# TCA0372_3x.net
KiCad netlist of a schematic drawn in EAGLE
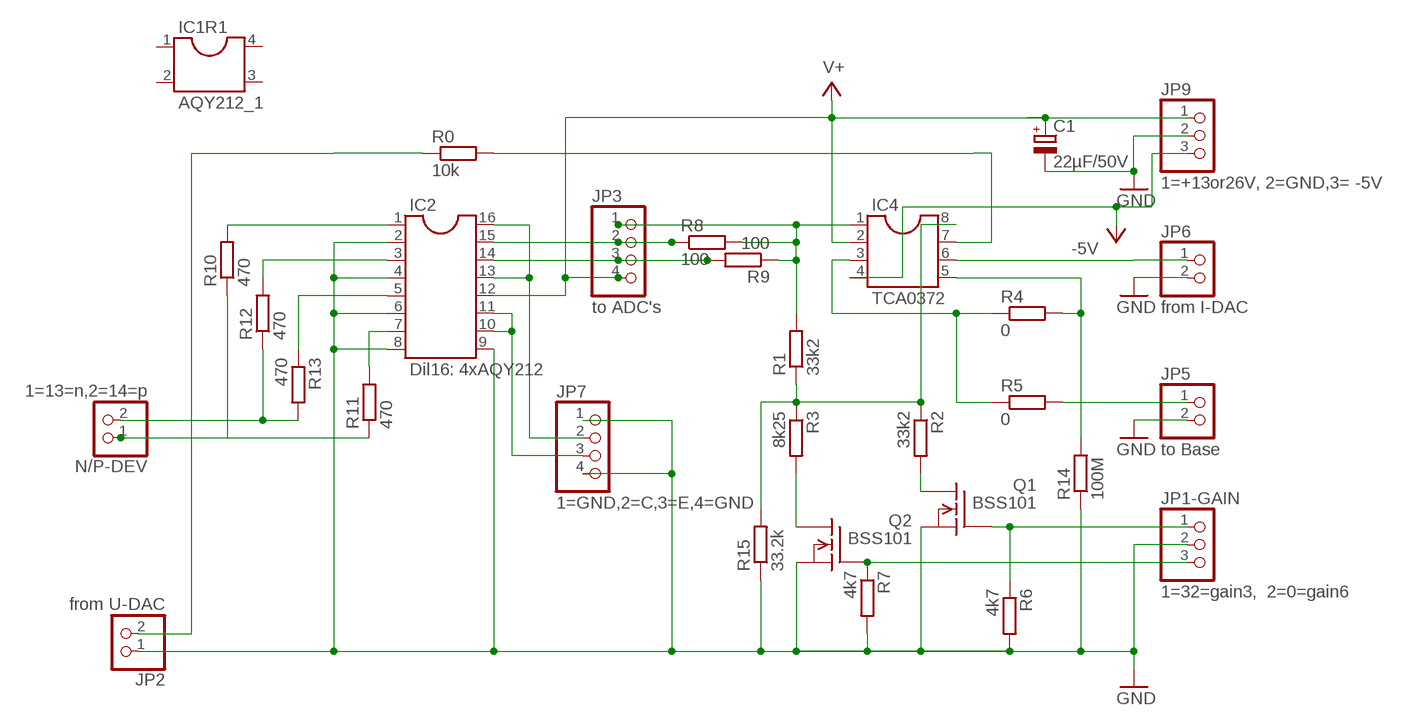
[diagram p0: schematic, sheet 1]

(export (version "E")
  (design (tool "Eeschema 10.0.6"))
  (components
    (comp (ref "C1")
      (value "22µF/50V")
      (footprint "eagle-import:E5-10,5")
      (libsource (lib "eagle-import") (part "CPOL-EUE5-10.5"))
    )
    (comp (ref "IC1R1")
      (value "AQY212_1")
      (footprint "eagle-import:SOCKET-04")
      (libsource (lib "eagle-import") (part "DIL4S"))
    )
    (comp (ref "IC2")
      (value "Dil16: 4xAQY212")
      (footprint "eagle-import:SOCKET-16")
      (libsource (lib "eagle-import") (part "DIL16S"))
    )
    (comp (ref "IC4")
      (value "TCA0372")
      (footprint "eagle-import:SOCKET-08")
      (libsource (lib "eagle-import") (part "DIL8S"))
    )
    (comp (ref "JP1-GAIN")
      (value "1=32=gain3, 2=0=gain6")
      (footprint "eagle-import:1X03")
      (libsource (lib "eagle-import") (part "PINHD-1X3"))
    )
    (comp (ref "JP2")
      (value "from U-DAC")
      (footprint "eagle-import:1X02")
      (libsource (lib "eagle-import") (part "PINHD-1X2"))
    )
    (comp (ref "JP3")
      (value "to ADC's")
      (footprint "eagle-import:1X04")
      (libsource (lib "eagle-import") (part "PINHD-1X4"))
    )
    (comp (ref "JP5")
      (value "to Base")
      (footprint "eagle-import:1X02")
      (libsource (lib "eagle-import") (part "PINHD-1X2"))
    )
    (comp (ref "JP6")
      (value "from I-DAC")
      (footprint "eagle-import:1X02")
      (libsource (lib "eagle-import") (part "PINHD-1X2"))
    )
    (comp (ref "JP7")
      (value "1=GND,2=C,3=E,4=GND")
      (footprint "eagle-import:1X04")
      (libsource (lib "eagle-import") (part "PINHD-1X4"))
    )
    (comp (ref "JP9")
      (value "1=+13or26V, 2=GND,3= -5V")
      (footprint "eagle-import:1X03")
      (libsource (lib "eagle-import") (part "PINHD-1X3"))
    )
    (comp (ref "N/P-DEV")
      (value "1=13=n,2=14=p")
      (footprint "eagle-import:1X02")
      (libsource (lib "eagle-import") (part "PINHD-1X2"))
    )
    (comp (ref "Q1")
      (value "BSS101")
      (footprint "eagle-import:TO92")
      (libsource (lib "eagle-import") (part "BSS101"))
    )
    (comp (ref "Q2")
      (value "BSS101")
      (footprint "eagle-import:TO92")
      (libsource (lib "eagle-import") (part "BSS101"))
    )
    (comp (ref "R0")
      (value "10k")
      (footprint "eagle-import:0207_7")
      (libsource (lib "eagle-import") (part "R-EU_0207/7"))
    )
    (comp (ref "R1")
      (value "33k2")
      (footprint "eagle-import:0207_7")
      (libsource (lib "eagle-import") (part "R-EU_0207/7"))
    )
    (comp (ref "R2")
      (value "33k2")
      (footprint "eagle-import:0207_7")
      (libsource (lib "eagle-import") (part "R-EU_0207/7"))
    )
    (comp (ref "R3")
      (value "8k25")
      (footprint "eagle-import:0207_7")
      (libsource (lib "eagle-import") (part "R-EU_0207/7"))
    )
    (comp (ref "R4")
      (value "0")
      (footprint "eagle-import:0207_7")
      (libsource (lib "eagle-import") (part "R-EU_0207/7"))
    )
    (comp (ref "R5")
      (value "0")
      (footprint "eagle-import:0207_7")
      (libsource (lib "eagle-import") (part "R-EU_0207/7"))
    )
    (comp (ref "R6")
      (value "4k7")
      (footprint "eagle-import:0207_7")
      (libsource (lib "eagle-import") (part "R-EU_0207/7"))
    )
    (comp (ref "R7")
      (value "4k7")
      (footprint "eagle-import:0207_7")
      (libsource (lib "eagle-import") (part "R-EU_0207/7"))
    )
    (comp (ref "R8")
      (value "100")
      (footprint "eagle-import:0207_7")
      (libsource (lib "eagle-import") (part "R-EU_0207/7"))
    )
    (comp (ref "R9")
      (value "100")
      (footprint "eagle-import:0207_7")
      (libsource (lib "eagle-import") (part "R-EU_0207/7"))
    )
    (comp (ref "R10")
      (value "470")
      (footprint "eagle-import:0207_7")
      (libsource (lib "eagle-import") (part "R-EU_0207/7"))
    )
    (comp (ref "R11")
      (value "470")
      (footprint "eagle-import:0207_7")
      (libsource (lib "eagle-import") (part "R-EU_0207/7"))
    )
    (comp (ref "R12")
      (value "470")
      (footprint "eagle-import:0207_7")
      (libsource (lib "eagle-import") (part "R-EU_0207/7"))
    )
    (comp (ref "R13")
      (value "470")
      (footprint "eagle-import:0207_7")
      (libsource (lib "eagle-import") (part "R-EU_0207/7"))
    )
    (comp (ref "R14")
      (value "100M")
      (footprint "eagle-import:0207_7")
      (libsource (lib "eagle-import") (part "R-EU_0207/7"))
    )
    (comp (ref "R15")
      (value "33.2k")
      (footprint "eagle-import:0207_7")
      (libsource (lib "eagle-import") (part "R-EU_0207/7"))
    )
  )
  (nets
    (net (code "1") (name "-5V") (class "Default")
      (node (ref "IC4") (pin "4") (pinfunction "4_4") (pintype "passive"))
      (node (ref "JP9") (pin "3") (pinfunction "3_3") (pintype "passive"))
    )
    (net (code "2") (name "GND") (class "Default")
      (node (ref "C1") (pin "-") (pinfunction "-_-") (pintype "passive"))
      (node (ref "IC2") (pin "2") (pinfunction "2_2") (pintype "passive"))
      (node (ref "IC2") (pin "4") (pinfunction "4_4") (pintype "passive"))
      (node (ref "IC2") (pin "6") (pinfunction "6_6") (pintype "passive"))
      (node (ref "IC2") (pin "8") (pinfunction "8_8") (pintype "passive"))
      (node (ref "IC2") (pin "9") (pinfunction "9_9") (pintype "passive"))
      (node (ref "JP1-GAIN") (pin "2") (pinfunction "2_2") (pintype "passive"))
      (node (ref "JP2") (pin "1") (pinfunction "1_1") (pintype "passive"))
      (node (ref "JP5") (pin "2") (pinfunction "2_2") (pintype "passive"))
      (node (ref "JP6") (pin "2") (pinfunction "2_2") (pintype "passive"))
      (node (ref "JP7") (pin "1") (pinfunction "1_1") (pintype "passive"))
      (node (ref "JP7") (pin "4") (pinfunction "4_4") (pintype "passive"))
      (node (ref "JP9") (pin "2") (pinfunction "2_2") (pintype "passive"))
      (node (ref "Q1") (pin "1") (pinfunction "S_1") (pintype "passive"))
      (node (ref "Q2") (pin "1") (pinfunction "S_1") (pintype "passive"))
      (node (ref "R14") (pin "1") (pinfunction "1_1") (pintype "passive"))
      (node (ref "R15") (pin "1") (pinfunction "1_1") (pintype "passive"))
      (node (ref "R6") (pin "2") (pinfunction "2_2") (pintype "passive"))
      (node (ref "R7") (pin "2") (pinfunction "2_2") (pintype "passive"))
    )
    (net (code "3") (name "Net-(IC2-Pad1)") (class "Default")
      (node (ref "IC2") (pin "1") (pinfunction "1_1") (pintype "passive"))
      (node (ref "R10") (pin "2") (pinfunction "2_2") (pintype "passive"))
    )
    (net (code "4") (name "Net-(IC2-Pad3)") (class "Default")
      (node (ref "IC2") (pin "3") (pinfunction "3_3") (pintype "passive"))
      (node (ref "R12") (pin "2") (pinfunction "2_2") (pintype "passive"))
    )
    (net (code "5") (name "Net-(IC2-Pad5)") (class "Default")
      (node (ref "IC2") (pin "5") (pinfunction "5_5") (pintype "passive"))
      (node (ref "R13") (pin "1") (pinfunction "1_1") (pintype "passive"))
    )
    (net (code "6") (name "Net-(IC2-Pad7)") (class "Default")
      (node (ref "IC2") (pin "7") (pinfunction "7_7") (pintype "passive"))
      (node (ref "R11") (pin "2") (pinfunction "2_2") (pintype "passive"))
    )
    (net (code "7") (name "Net-(IC2-Pad10)") (class "Default")
      (node (ref "IC2") (pin "10") (pinfunction "10_10") (pintype "passive"))
      (node (ref "IC2") (pin "11") (pinfunction "11_11") (pintype "passive"))
      (node (ref "JP7") (pin "3") (pinfunction "3_3") (pintype "passive"))
    )
    (net (code "8") (name "Net-(IC2-Pad13)") (class "Default")
      (node (ref "IC2") (pin "13") (pinfunction "13_13") (pintype "passive"))
      (node (ref "IC2") (pin "16") (pinfunction "16_16") (pintype "passive"))
      (node (ref "JP7") (pin "2") (pinfunction "2_2") (pintype "passive"))
    )
    (net (code "9") (name "Net-(IC2-Pad14)") (class "Default")
      (node (ref "IC2") (pin "14") (pinfunction "14_14") (pintype "passive"))
      (node (ref "JP3") (pin "3") (pinfunction "3_3") (pintype "passive"))
      (node (ref "R9") (pin "2") (pinfunction "2_2") (pintype "passive"))
    )
    (net (code "10") (name "Net-(IC2-Pad15)") (class "Default")
      (node (ref "IC2") (pin "15") (pinfunction "15_15") (pintype "passive"))
      (node (ref "JP3") (pin "2") (pinfunction "2_2") (pintype "passive"))
      (node (ref "R8") (pin "1") (pinfunction "1_1") (pintype "passive"))
    )
    (net (code "11") (name "Net-(IC4-Pad1)") (class "Default")
      (node (ref "IC4") (pin "1") (pinfunction "1_1") (pintype "passive"))
      (node (ref "JP3") (pin "1") (pinfunction "1_1") (pintype "passive"))
      (node (ref "R1") (pin "2") (pinfunction "2_2") (pintype "passive"))
      (node (ref "R8") (pin "2") (pinfunction "2_2") (pintype "passive"))
      (node (ref "R9") (pin "1") (pinfunction "1_1") (pintype "passive"))
    )
    (net (code "12") (name "Net-(IC4-Pad3)") (class "Default")
      (node (ref "IC4") (pin "3") (pinfunction "3_3") (pintype "passive"))
      (node (ref "R4") (pin "1") (pinfunction "1_1") (pintype "passive"))
      (node (ref "R5") (pin "1") (pinfunction "1_1") (pintype "passive"))
    )
    (net (code "13") (name "Net-(IC4-Pad5)") (class "Default")
      (node (ref "IC4") (pin "5") (pinfunction "5_5") (pintype "passive"))
      (node (ref "R14") (pin "2") (pinfunction "2_2") (pintype "passive"))
      (node (ref "R4") (pin "2") (pinfunction "2_2") (pintype "passive"))
    )
    (net (code "14") (name "Net-(IC4-Pad6)") (class "Default")
      (node (ref "IC4") (pin "6") (pinfunction "6_6") (pintype "passive"))
      (node (ref "JP6") (pin "1") (pinfunction "1_1") (pintype "passive"))
    )
    (net (code "15") (name "Net-(IC4-Pad7)") (class "Default")
      (node (ref "IC4") (pin "7") (pinfunction "7_7") (pintype "passive"))
      (node (ref "R0") (pin "2") (pinfunction "2_2") (pintype "passive"))
    )
    (net (code "16") (name "Net-(IC4-Pad8)") (class "Default")
      (node (ref "IC4") (pin "8") (pinfunction "8_8") (pintype "passive"))
      (node (ref "R1") (pin "1") (pinfunction "1_1") (pintype "passive"))
      (node (ref "R15") (pin "2") (pinfunction "2_2") (pintype "passive"))
      (node (ref "R2") (pin "1") (pinfunction "1_1") (pintype "passive"))
      (node (ref "R3") (pin "1") (pinfunction "1_1") (pintype "passive"))
    )
    (net (code "17") (name "Net-(JP2-Pad2)") (class "Default")
      (node (ref "JP2") (pin "2") (pinfunction "2_2") (pintype "passive"))
      (node (ref "R0") (pin "1") (pinfunction "1_1") (pintype "passive"))
    )
    (net (code "18") (name "Net-(JP5-Pad1)") (class "Default")
      (node (ref "JP5") (pin "1") (pinfunction "1_1") (pintype "passive"))
      (node (ref "R5") (pin "2") (pinfunction "2_2") (pintype "passive"))
    )
    (net (code "19") (name "Net-(N/P-DEV-Pad1)") (class "Default")
      (node (ref "N/P-DEV") (pin "1") (pinfunction "1_1") (pintype "passive"))
      (node (ref "R10") (pin "1") (pinfunction "1_1") (pintype "passive"))
      (node (ref "R11") (pin "1") (pinfunction "1_1") (pintype "passive"))
    )
    (net (code "20") (name "Net-(N/P-DEV-Pad2)") (class "Default")
      (node (ref "N/P-DEV") (pin "2") (pinfunction "2_2") (pintype "passive"))
      (node (ref "R12") (pin "1") (pinfunction "1_1") (pintype "passive"))
      (node (ref "R13") (pin "2") (pinfunction "2_2") (pintype "passive"))
    )
    (net (code "21") (name "Net-(Q1-D)") (class "Default")
      (node (ref "Q1") (pin "3") (pinfunction "D_3") (pintype "passive"))
      (node (ref "R2") (pin "2") (pinfunction "2_2") (pintype "passive"))
    )
    (net (code "22") (name "Net-(Q1-G)") (class "Default")
      (node (ref "JP1-GAIN") (pin "1") (pinfunction "1_1") (pintype "passive"))
      (node (ref "Q1") (pin "2") (pinfunction "G_2") (pintype "passive"))
      (node (ref "R6") (pin "1") (pinfunction "1_1") (pintype "passive"))
    )
    (net (code "23") (name "Net-(Q2-D)") (class "Default")
      (node (ref "Q2") (pin "3") (pinfunction "D_3") (pintype "passive"))
      (node (ref "R3") (pin "2") (pinfunction "2_2") (pintype "passive"))
    )
    (net (code "24") (name "Net-(Q2-G)") (class "Default")
      (node (ref "JP1-GAIN") (pin "3") (pinfunction "3_3") (pintype "passive"))
      (node (ref "Q2") (pin "2") (pinfunction "G_2") (pintype "passive"))
      (node (ref "R7") (pin "1") (pinfunction "1_1") (pintype "passive"))
    )
    (net (code "25") (name "V+") (class "Default")
      (node (ref "C1") (pin "+") (pinfunction "+_+") (pintype "passive"))
      (node (ref "IC2") (pin "12") (pinfunction "12_12") (pintype "passive"))
      (node (ref "IC4") (pin "2") (pinfunction "2_2") (pintype "passive"))
      (node (ref "JP3") (pin "4") (pinfunction "4_4") (pintype "passive"))
      (node (ref "JP9") (pin "1") (pinfunction "1_1") (pintype "passive"))
    )
    (net (code "26") (name "unconnected-(IC1R1-Pad1)") (class "Default")
      (node (ref "IC1R1") (pin "1") (pinfunction "1_1") (pintype "passive"))
    )
    (net (code "27") (name "unconnected-(IC1R1-Pad2)") (class "Default")
      (node (ref "IC1R1") (pin "2") (pinfunction "2_2") (pintype "passive"))
    )
    (net (code "28") (name "unconnected-(IC1R1-Pad3)") (class "Default")
      (node (ref "IC1R1") (pin "3") (pinfunction "3_3") (pintype "passive"))
    )
    (net (code "29") (name "unconnected-(IC1R1-Pad4)") (class "Default")
      (node (ref "IC1R1") (pin "4") (pinfunction "4_4") (pintype "passive"))
    )
  )
)
